# ETH-PHY.net
KiCad netlist of a schematic drawn in Altium Designer
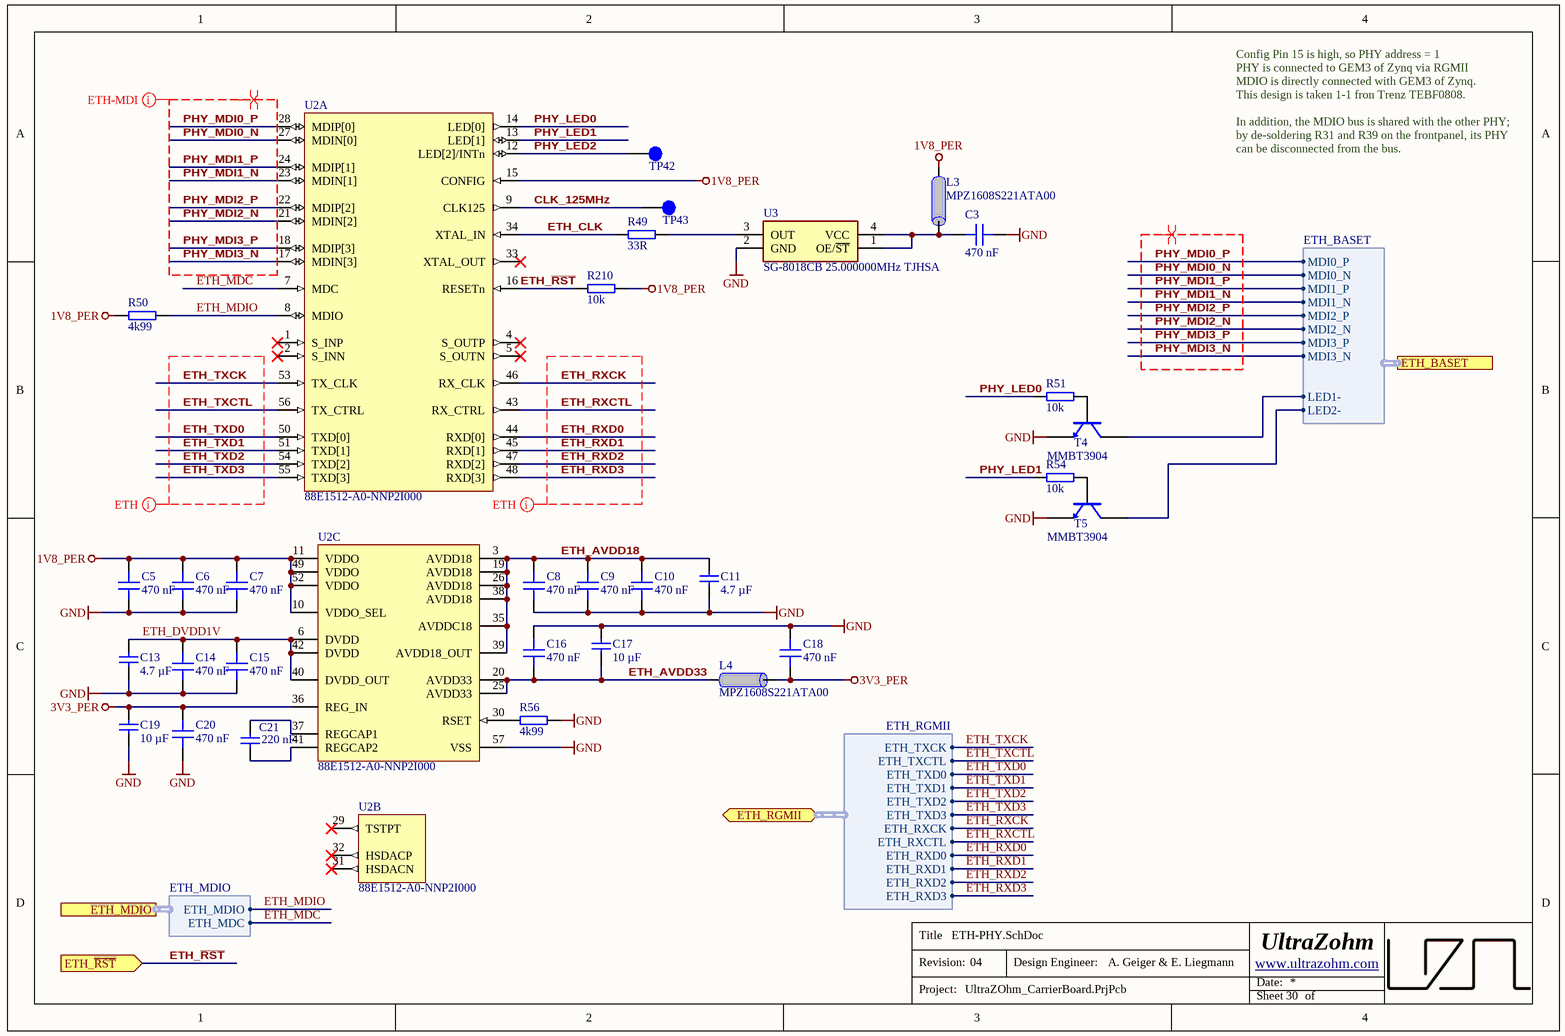
[diagram p0: ETH-PHY.SchDoc]

(export (version "E")
  (design (tool "Eeschema 10.0.6"))
  (components
    (comp (ref "C3")
      (value "470 nF")
      (footprint "C_0603_TE")
      (description "Capacitor 0603, 50 VDC, 470 nF, X5R")
      (fields
        (field (name "MANUFACTURER PART NUMBER") "CL10A474KB8NNNC")
        (field (name "MANUFACTURER") "Samsung Electro-Mechanics")
        (field (name "CREATED FROM") "AGeiger")
      )
      (libsource (lib "user") (part "Capacitor"))
    )
    (comp (ref "C5")
      (value "470 nF")
      (footprint "C_0603_TE")
      (description "Capacitor 0603, 50 VDC, 470 nF, X5R")
      (fields
        (field (name "MANUFACTURER PART NUMBER") "CL10A474KB8NNNC")
        (field (name "MANUFACTURER") "Samsung Electro-Mechanics")
        (field (name "CREATED FROM") "AGeiger")
      )
      (libsource (lib "user") (part "Capacitor"))
    )
    (comp (ref "C6")
      (value "470 nF")
      (footprint "C_0603_TE")
      (description "Capacitor 0603, 50 VDC, 470 nF, X5R")
      (fields
        (field (name "MANUFACTURER PART NUMBER") "CL10A474KB8NNNC")
        (field (name "MANUFACTURER") "Samsung Electro-Mechanics")
        (field (name "CREATED FROM") "AGeiger")
      )
      (libsource (lib "user") (part "Capacitor"))
    )
    (comp (ref "C7")
      (value "470 nF")
      (footprint "C_0603_TE")
      (description "Capacitor 0603, 50 VDC, 470 nF, X5R")
      (fields
        (field (name "MANUFACTURER PART NUMBER") "CL10A474KB8NNNC")
        (field (name "MANUFACTURER") "Samsung Electro-Mechanics")
        (field (name "CREATED FROM") "AGeiger")
      )
      (libsource (lib "user") (part "Capacitor"))
    )
    (comp (ref "C8")
      (value "470 nF")
      (footprint "C_0603_TE")
      (description "Capacitor 0603, 50 VDC, 470 nF, X5R")
      (fields
        (field (name "MANUFACTURER PART NUMBER") "CL10A474KB8NNNC")
        (field (name "MANUFACTURER") "Samsung Electro-Mechanics")
        (field (name "CREATED FROM") "AGeiger")
      )
      (libsource (lib "user") (part "Capacitor"))
    )
    (comp (ref "C9")
      (value "470 nF")
      (footprint "C_0603_TE")
      (description "Capacitor 0603, 50 VDC, 470 nF, X5R")
      (fields
        (field (name "MANUFACTURER PART NUMBER") "CL10A474KB8NNNC")
        (field (name "MANUFACTURER") "Samsung Electro-Mechanics")
        (field (name "CREATED FROM") "AGeiger")
      )
      (libsource (lib "user") (part "Capacitor"))
    )
    (comp (ref "C10")
      (value "470 nF")
      (footprint "C_0603_TE")
      (description "Capacitor 0603, 50 VDC, 470 nF, X5R")
      (fields
        (field (name "MANUFACTURER PART NUMBER") "CL10A474KB8NNNC")
        (field (name "MANUFACTURER") "Samsung Electro-Mechanics")
        (field (name "CREATED FROM") "AGeiger")
      )
      (libsource (lib "user") (part "Capacitor"))
    )
    (comp (ref "C11")
      (value "4.7 µF")
      (footprint "C_0603_TE")
      (description "Generic capacitor")
      (fields
        (field (name "TOLERANCE") "10 %")
        (field (name "MANUFACTURER PART NUMBER") "UZgen_C_0603_4.7uF_16V_X5R")
        (field (name "CREATED FROM") "MGeier")
      )
      (libsource (lib "user") (part "CAP-NP"))
    )
    (comp (ref "C13")
      (value "4.7 µF")
      (footprint "C_0603_TE")
      (description "Generic capacitor")
      (fields
        (field (name "TOLERANCE") "10 %")
        (field (name "MANUFACTURER PART NUMBER") "UZgen_C_0603_4.7uF_16V_X5R")
        (field (name "CREATED FROM") "MGeier")
      )
      (libsource (lib "user") (part "CAP-NP"))
    )
    (comp (ref "C14")
      (value "470 nF")
      (footprint "C_0603_TE")
      (description "Capacitor 0603, 50 VDC, 470 nF, X5R")
      (fields
        (field (name "MANUFACTURER PART NUMBER") "CL10A474KB8NNNC")
        (field (name "MANUFACTURER") "Samsung Electro-Mechanics")
        (field (name "CREATED FROM") "AGeiger")
      )
      (libsource (lib "user") (part "Capacitor"))
    )
    (comp (ref "C15")
      (value "470 nF")
      (footprint "C_0603_TE")
      (description "Capacitor 0603, 50 VDC, 470 nF, X5R")
      (fields
        (field (name "MANUFACTURER PART NUMBER") "CL10A474KB8NNNC")
        (field (name "MANUFACTURER") "Samsung Electro-Mechanics")
        (field (name "CREATED FROM") "AGeiger")
      )
      (libsource (lib "user") (part "Capacitor"))
    )
    (comp (ref "C16")
      (value "470 nF")
      (footprint "C_0603_TE")
      (description "Capacitor 0603, 50 VDC, 470 nF, X5R")
      (fields
        (field (name "MANUFACTURER PART NUMBER") "CL10A474KB8NNNC")
        (field (name "MANUFACTURER") "Samsung Electro-Mechanics")
        (field (name "CREATED FROM") "AGeiger")
      )
      (libsource (lib "user") (part "Capacitor"))
    )
    (comp (ref "C17")
      (value "10 µF")
      (footprint "C_0603_TE")
      (description "Generic capacitor")
      (fields
        (field (name "MANUFACTURER PART NUMBER") "UZgen_C_0603_10uF_6.3V_X7R")
        (field (name "MANUFACTURER") "UZgen")
        (field (name "CREATED FROM") "UZgenTool")
      )
      (libsource (lib "user") (part "CAP-NP"))
    )
    (comp (ref "C18")
      (value "470 nF")
      (footprint "C_0603_TE")
      (description "Capacitor 0603, 50 VDC, 470 nF, X5R")
      (fields
        (field (name "MANUFACTURER PART NUMBER") "CL10A474KB8NNNC")
        (field (name "MANUFACTURER") "Samsung Electro-Mechanics")
        (field (name "CREATED FROM") "AGeiger")
      )
      (libsource (lib "user") (part "Capacitor"))
    )
    (comp (ref "C19")
      (value "10 µF")
      (footprint "C_0603_TE")
      (description "Generic capacitor")
      (fields
        (field (name "MANUFACTURER PART NUMBER") "UZgen_C_0603_10uF_6.3V_X7R")
        (field (name "MANUFACTURER") "UZgen")
        (field (name "CREATED FROM") "UZgenTool")
      )
      (libsource (lib "user") (part "CAP-NP"))
    )
    (comp (ref "C20")
      (value "470 nF")
      (footprint "C_0603_TE")
      (description "Capacitor 0603, 50 VDC, 470 nF, X5R")
      (fields
        (field (name "MANUFACTURER PART NUMBER") "CL10A474KB8NNNC")
        (field (name "MANUFACTURER") "Samsung Electro-Mechanics")
        (field (name "CREATED FROM") "AGeiger")
      )
      (libsource (lib "user") (part "Capacitor"))
    )
    (comp (ref "C21")
      (value "220 nF")
      (footprint "C_0603_TE")
      (description "Generic capacitor")
      (fields
        (field (name "TOLERANCE") "10 %")
        (field (name "VOLTAGE") "50V")
        (field (name "CREATED FROM") "UZgenTool")
      )
      (libsource (lib "user") (part "CAP-NP"))
    )
    (comp (ref "L3")
      (value "MPZ1608S221ATA00")
      (footprint "RES 0603_1608")
      (description "Ferritperle, 0603, 220 ohm, 2.2 A, Baureihe MPZ, 0.05 ohm, ± 25%")
      (fields
        (field (name "MANUFACTURER") "TDK")
        (field (name "LCSC PART NUMBER") "C76815")
        (field (name "CREATED FROM") "MGremer")
      )
      (libsource (lib "") (part "Ferrite_Bead_1"))
    )
    (comp (ref "L4")
      (value "MPZ1608S221ATA00")
      (footprint "RES 0603_1608")
      (description "Ferritperle, 0603, 220 ohm, 2.2 A, Baureihe MPZ, 0.05 ohm, ± 25%")
      (fields
        (field (name "MANUFACTURER") "TDK")
        (field (name "LCSC PART NUMBER") "C76815")
        (field (name "CREATED FROM") "MGremer")
      )
      (libsource (lib "user") (part "Ferrite_Bead"))
    )
    (comp (ref "R49")
      (value "33R")
      (footprint "R_0603_TE")
      (description "Generic resistor")
      (fields
        (field (name "TOLERANCE") "1 %")
        (field (name "MANUFACTURER PART NUMBER") "UZgen_R_0603_33R")
        (field (name "CREATED FROM") "UZgenTool")
      )
      (libsource (lib "user") (part "RES"))
    )
    (comp (ref "R50")
      (value "4k99")
      (footprint "RES 0603_1608")
      (fields
        (field (name "TOLERANCE") "1%")
        (field (name "MANUFACTURER PART NUMBER") "0603WAF4991T5E")
        (field (name "MANUFACTURER") "UNI-ROYAL(Uniroyal Elec)")
        (field (name "CREATED FROM") "NDiringer")
      )
      (libsource (lib "user") (part "Resistor"))
    )
    (comp (ref "R51")
      (value "10k")
      (footprint "R_0603_TE")
      (description "Generic resistor")
      (fields
        (field (name "TOLERANCE") "1 %")
        (field (name "MANUFACTURER PART NUMBER") "UZgen_R_0603_10k")
        (field (name "CREATED FROM") "AGeiger")
      )
      (libsource (lib "user") (part "RES"))
    )
    (comp (ref "R54")
      (value "10k")
      (footprint "R_0603_TE")
      (description "Generic resistor")
      (fields
        (field (name "TOLERANCE") "1 %")
        (field (name "MANUFACTURER PART NUMBER") "UZgen_R_0603_10k")
        (field (name "CREATED FROM") "AGeiger")
      )
      (libsource (lib "user") (part "RES"))
    )
    (comp (ref "R56")
      (value "4k99")
      (footprint "RES 0603_1608")
      (fields
        (field (name "TOLERANCE") "1%")
        (field (name "MANUFACTURER PART NUMBER") "0603WAF4991T5E")
        (field (name "MANUFACTURER") "UNI-ROYAL(Uniroyal Elec)")
        (field (name "CREATED FROM") "NDiringer")
      )
      (libsource (lib "user") (part "Resistor"))
    )
    (comp (ref "R210")
      (value "10k")
      (footprint "R_0603_TE")
      (description "Generic resistor")
      (fields
        (field (name "TOLERANCE") "1 %")
        (field (name "MANUFACTURER PART NUMBER") "UZgen_R_0603_10k")
        (field (name "CREATED FROM") "AGeiger")
      )
      (libsource (lib "user") (part "RES"))
    )
    (comp (ref "T4")
      (value "MMBT3904")
      (footprint "SOT95P280X145-3N")
      (fields
        (field (name "MANUFACTURER") "Jiangsu Changjing Electronics Technology Co., Ltd.")
        (field (name "LCSC PART NUMBER") "C20526")
        (field (name "CREATED FROM") "NDiringer")
      )
      (libsource (lib "user") (part "NPN-SOT23"))
    )
    (comp (ref "T5")
      (value "MMBT3904")
      (footprint "SOT95P280X145-3N")
      (fields
        (field (name "MANUFACTURER") "Jiangsu Changjing Electronics Technology Co., Ltd.")
        (field (name "LCSC PART NUMBER") "C20526")
        (field (name "CREATED FROM") "NDiringer")
      )
      (libsource (lib "user") (part "NPN-SOT23"))
    )
    (comp (ref "TP42")
      (value "Testpoint 1mm")
      (footprint "TP_1mm")
      (fields
        (field (name "MANUFACTURER PART NUMBER") "NULL")
        (field (name "CREATED") "2018_06_25_AGeiger")
        (field (name "CREATED FROM") "AGeiger")
      )
      (libsource (lib "user") (part "TP_1mm"))
    )
    (comp (ref "TP43")
      (value "Testpoint 1mm")
      (footprint "TP_1mm")
      (fields
        (field (name "MANUFACTURER PART NUMBER") "NULL")
        (field (name "CREATED") "2018_06_25_AGeiger")
        (field (name "CREATED FROM") "AGeiger")
      )
      (libsource (lib "user") (part "TP_1mm"))
    )
    (comp (ref "U2")
      (value "88E1512-A0-NNP2I000")
      (footprint "QFN50P800X800X100-57N")
      (description "Ethernet ICs Single-Port EEE GE PHY w/SGMII in 56-pin QFN")
      (fields
        (field (name "MANUFACTURER") "Marvell")
        (field (name "LCSC PART NUMBER") "C713256")
        (field (name "CREATED FROM") "MGremer")
      )
      (libsource (lib "user") (part "88E1512"))
    )
    (comp (ref "U3")
      (value "SG-8018CB 25.000000MHz TJHSA")
      (footprint "SMD5032-4P")
      (description "±50ppm 1.8V~3.3V 25MHz SMD5032-4P Programmable Oscillators ROHS")
      (fields
        (field (name "MANUFACTURER") "Seiko Epson")
        (field (name "LCSC PART NUMBER") "C390471")
        (field (name "CREATED FROM") "FRosner")
      )
      (libsource (lib "user") (part "SG-8018CB"))
    )
  )
  (nets
    (net (code "3") (name "/CLK_125MHz") (class "Default")
      (node (ref "TP43") (pin "1") (pintype "passive"))
      (node (ref "U2") (pin "9") (pinfunction "CLK125_9") (pintype "output"))
    )
    (net (code "4") (name "/ETH_AVDD18") (class "Default")
      (node (ref "C10") (pin "1") (pinfunction "1_1") (pintype "passive"))
      (node (ref "C11") (pin "1") (pinfunction "1_1") (pintype "passive"))
      (node (ref "C8") (pin "1") (pinfunction "1_1") (pintype "passive"))
      (node (ref "C9") (pin "1") (pinfunction "1_1") (pintype "passive"))
      (node (ref "U2") (pin "19") (pinfunction "AVDD18_19") (pintype "power_in"))
      (node (ref "U2") (pin "26") (pinfunction "AVDD18_26") (pintype "power_in"))
      (node (ref "U2") (pin "3") (pinfunction "AVDD18_3") (pintype "power_in"))
      (node (ref "U2") (pin "35") (pinfunction "AVDDC18_35") (pintype "power_in"))
      (node (ref "U2") (pin "38") (pinfunction "AVDD18_38") (pintype "power_in"))
      (node (ref "U2") (pin "39") (pinfunction "AVDD18_OUT_39") (pintype "power_in"))
    )
    (net (code "5") (name "/ETH_AVDD33") (class "Default")
      (node (ref "C16") (pin "2") (pinfunction "2_2") (pintype "passive"))
      (node (ref "C17") (pin "2") (pinfunction "2_2") (pintype "passive"))
      (node (ref "L4") (pin "1") (pinfunction "1_1") (pintype "passive"))
      (node (ref "U2") (pin "20") (pinfunction "AVDD33_20") (pintype "power_in"))
      (node (ref "U2") (pin "25") (pinfunction "AVDD33_25") (pintype "power_in"))
    )
    (net (code "6") (name "/ETH_CLK") (class "Default")
      (node (ref "R49") (pin "1") (pinfunction "1_1") (pintype "passive"))
      (node (ref "U2") (pin "34") (pinfunction "XTAL_IN_34") (pintype "input"))
    )
    (net (code "7") (name "/ETH_DVDD1V") (class "Default")
      (node (ref "C13") (pin "1") (pinfunction "1_1") (pintype "passive"))
      (node (ref "C14") (pin "1") (pinfunction "1_1") (pintype "passive"))
      (node (ref "C15") (pin "1") (pinfunction "1_1") (pintype "passive"))
      (node (ref "U2") (pin "40") (pinfunction "DVDD_OUT_40") (pintype "power_in"))
      (node (ref "U2") (pin "42") (pinfunction "DVDD_42") (pintype "power_in"))
      (node (ref "U2") (pin "6") (pinfunction "DVDD_6") (pintype "power_in"))
    )
    (net (code "8") (name "/ETH_MDC") (class "Default")
      (node (ref "U2") (pin "7") (pinfunction "MDC_7") (pintype "input"))
    )
    (net (code "9") (name "/ETH_MDIO") (class "Default")
      (node (ref "R50") (pin "2") (pinfunction "2_2") (pintype "passive"))
      (node (ref "U2") (pin "8") (pinfunction "MDIO_8") (pintype "bidirectional"))
    )
    (net (code "10") (name "/ETH_RXCK") (class "Default")
      (node (ref "U2") (pin "46") (pinfunction "RX_CLK_46") (pintype "output"))
    )
    (net (code "11") (name "/ETH_RXCTL") (class "Default")
      (node (ref "U2") (pin "43") (pinfunction "RX_CTRL_43") (pintype "output"))
    )
    (net (code "12") (name "/ETH_RXD0") (class "Default")
      (node (ref "U2") (pin "44") (pinfunction "RXD[0]_44") (pintype "output"))
    )
    (net (code "13") (name "/ETH_RXD1") (class "Default")
      (node (ref "U2") (pin "45") (pinfunction "RXD[1]_45") (pintype "output"))
    )
    (net (code "14") (name "/ETH_RXD2") (class "Default")
      (node (ref "U2") (pin "47") (pinfunction "RXD[2]_47") (pintype "output"))
    )
    (net (code "15") (name "/ETH_RXD3") (class "Default")
      (node (ref "U2") (pin "48") (pinfunction "RXD[3]_48") (pintype "output"))
    )
    (net (code "16") (name "/ETH_TXCK") (class "Default")
      (node (ref "U2") (pin "53") (pinfunction "TX_CLK_53") (pintype "input"))
    )
    (net (code "17") (name "/ETH_TXCTL") (class "Default")
      (node (ref "U2") (pin "56") (pinfunction "TX_CTRL_56") (pintype "input"))
    )
    (net (code "18") (name "/ETH_TXD0") (class "Default")
      (node (ref "U2") (pin "50") (pinfunction "TXD[0]_50") (pintype "input"))
    )
    (net (code "19") (name "/ETH_TXD1") (class "Default")
      (node (ref "U2") (pin "51") (pinfunction "TXD[1]_51") (pintype "input"))
    )
    (net (code "20") (name "/ETH_TXD2") (class "Default")
      (node (ref "U2") (pin "54") (pinfunction "TXD[2]_54") (pintype "input"))
    )
    (net (code "21") (name "/ETH_TXD3") (class "Default")
      (node (ref "U2") (pin "55") (pinfunction "TXD[3]_55") (pintype "input"))
    )
    (net (code "22") (name "/ETH_~{RST}") (class "Default")
      (node (ref "R210") (pin "1") (pinfunction "1_1") (pintype "passive"))
      (node (ref "U2") (pin "16") (pinfunction "RESETn_16") (pintype "input"))
    )
    (net (code "23") (name "/LED1-") (class "Default")
      (node (ref "T4") (pin "3") (pinfunction "COLLECTOR_3") (pintype "passive"))
    )
    (net (code "24") (name "/LED2-") (class "Default")
      (node (ref "T5") (pin "3") (pinfunction "COLLECTOR_3") (pintype "passive"))
    )
    (net (code "25") (name "/PHY_LED0") (class "Default")
      (node (ref "R51") (pin "1") (pinfunction "1_1") (pintype "passive"))
      (node (ref "U2") (pin "14") (pinfunction "LED[0]_14") (pintype "output"))
    )
    (net (code "26") (name "/PHY_LED1") (class "Default")
      (node (ref "R54") (pin "1") (pinfunction "1_1") (pintype "passive"))
      (node (ref "U2") (pin "13") (pinfunction "LED[1]_13") (pintype "bidirectional"))
    )
    (net (code "27") (name "/PHY_LED2") (class "Default")
      (node (ref "TP42") (pin "1") (pintype "passive"))
      (node (ref "U2") (pin "12") (pinfunction "LED[2]/INTn_12") (pintype "bidirectional"))
    )
    (net (code "28") (name "/PHY_MDI0_N") (class "Default")
      (node (ref "U2") (pin "27") (pinfunction "MDIN[0]_27") (pintype "bidirectional"))
    )
    (net (code "29") (name "/PHY_MDI0_P") (class "Default")
      (node (ref "U2") (pin "28") (pinfunction "MDIP[0]_28") (pintype "bidirectional"))
    )
    (net (code "30") (name "/PHY_MDI1_N") (class "Default")
      (node (ref "U2") (pin "23") (pinfunction "MDIN[1]_23") (pintype "bidirectional"))
    )
    (net (code "31") (name "/PHY_MDI1_P") (class "Default")
      (node (ref "U2") (pin "24") (pinfunction "MDIP[1]_24") (pintype "bidirectional"))
    )
    (net (code "32") (name "/PHY_MDI2_N") (class "Default")
      (node (ref "U2") (pin "21") (pinfunction "MDIN[2]_21") (pintype "bidirectional"))
    )
    (net (code "33") (name "/PHY_MDI2_P") (class "Default")
      (node (ref "U2") (pin "22") (pinfunction "MDIP[2]_22") (pintype "bidirectional"))
    )
    (net (code "34") (name "/PHY_MDI3_N") (class "Default")
      (node (ref "U2") (pin "17") (pinfunction "MDIN[3]_17") (pintype "bidirectional"))
    )
    (net (code "35") (name "/PHY_MDI3_P") (class "Default")
      (node (ref "U2") (pin "18") (pinfunction "MDIP[3]_18") (pintype "bidirectional"))
    )
    (net (code "39") (name "1V8_PER") (class "Default")
      (node (ref "C5") (pin "1") (pinfunction "1_1") (pintype "passive"))
      (node (ref "C6") (pin "1") (pinfunction "1_1") (pintype "passive"))
      (node (ref "C7") (pin "1") (pinfunction "1_1") (pintype "passive"))
      (node (ref "L3") (pin "1") (pinfunction "1_1") (pintype "passive"))
      (node (ref "R210") (pin "2") (pinfunction "2_2") (pintype "passive"))
      (node (ref "R50") (pin "1") (pinfunction "1_1") (pintype "passive"))
      (node (ref "U2") (pin "10") (pinfunction "VDDO_SEL_10") (pintype "power_in"))
      (node (ref "U2") (pin "11") (pinfunction "VDDO_11") (pintype "power_in"))
      (node (ref "U2") (pin "15") (pinfunction "CONFIG_15") (pintype "input"))
      (node (ref "U2") (pin "49") (pinfunction "VDDO_49") (pintype "power_in"))
      (node (ref "U2") (pin "52") (pinfunction "VDDO_52") (pintype "power_in"))
    )
    (net (code "40") (name "3V3_PER") (class "Default")
      (node (ref "C18") (pin "2") (pinfunction "2_2") (pintype "passive"))
      (node (ref "C19") (pin "1") (pinfunction "1_1") (pintype "passive"))
      (node (ref "C20") (pin "1") (pinfunction "1_1") (pintype "passive"))
      (node (ref "L4") (pin "2") (pinfunction "2_2") (pintype "passive"))
      (node (ref "U2") (pin "36") (pinfunction "REG_IN_36") (pintype "power_in"))
    )
    (net (code "41") (name "GND") (class "Default")
      (node (ref "C10") (pin "2") (pinfunction "2_2") (pintype "passive"))
      (node (ref "C11") (pin "2") (pinfunction "2_2") (pintype "passive"))
      (node (ref "C13") (pin "2") (pinfunction "2_2") (pintype "passive"))
      (node (ref "C14") (pin "2") (pinfunction "2_2") (pintype "passive"))
      (node (ref "C15") (pin "2") (pinfunction "2_2") (pintype "passive"))
      (node (ref "C16") (pin "1") (pinfunction "1_1") (pintype "passive"))
      (node (ref "C17") (pin "1") (pinfunction "1_1") (pintype "passive"))
      (node (ref "C18") (pin "1") (pinfunction "1_1") (pintype "passive"))
      (node (ref "C19") (pin "2") (pinfunction "2_2") (pintype "passive"))
      (node (ref "C20") (pin "2") (pinfunction "2_2") (pintype "passive"))
      (node (ref "C3") (pin "1") (pinfunction "1_1") (pintype "passive"))
      (node (ref "C5") (pin "2") (pinfunction "2_2") (pintype "passive"))
      (node (ref "C6") (pin "2") (pinfunction "2_2") (pintype "passive"))
      (node (ref "C7") (pin "2") (pinfunction "2_2") (pintype "passive"))
      (node (ref "C8") (pin "2") (pinfunction "2_2") (pintype "passive"))
      (node (ref "C9") (pin "2") (pinfunction "2_2") (pintype "passive"))
      (node (ref "R56") (pin "2") (pinfunction "2_2") (pintype "passive"))
      (node (ref "T4") (pin "2") (pinfunction "EMITTER_2") (pintype "passive"))
      (node (ref "T5") (pin "2") (pinfunction "EMITTER_2") (pintype "passive"))
      (node (ref "U2") (pin "57") (pinfunction "VSS_57") (pintype "power_in"))
      (node (ref "U3") (pin "2") (pinfunction "GND_2") (pintype "passive"))
    )
    (net (code "42") (name "Net-(T4-BASIS)") (class "Default")
      (node (ref "R51") (pin "2") (pinfunction "2_2") (pintype "passive"))
      (node (ref "T4") (pin "1") (pinfunction "BASIS_1") (pintype "passive"))
    )
    (net (code "43") (name "Net-(T5-BASIS)") (class "Default")
      (node (ref "R54") (pin "2") (pinfunction "2_2") (pintype "passive"))
      (node (ref "T5") (pin "1") (pinfunction "BASIS_1") (pintype "passive"))
    )
    (net (code "44") (name "Net-(U2C-REGCAP1)") (class "Default")
      (node (ref "C21") (pin "1") (pinfunction "1_1") (pintype "passive"))
      (node (ref "U2") (pin "37") (pinfunction "REGCAP1_37") (pintype "passive"))
    )
    (net (code "45") (name "Net-(U2C-REGCAP2)") (class "Default")
      (node (ref "C21") (pin "2") (pinfunction "2_2") (pintype "passive"))
      (node (ref "U2") (pin "41") (pinfunction "REGCAP2_41") (pintype "passive"))
    )
    (net (code "46") (name "Net-(U2C-RSET)") (class "Default")
      (node (ref "R56") (pin "1") (pinfunction "1_1") (pintype "passive"))
      (node (ref "U2") (pin "30") (pinfunction "RSET_30") (pintype "input"))
    )
    (net (code "47") (name "Net-(U3-OE{slash}~{ST})") (class "Default")
      (node (ref "C3") (pin "2") (pinfunction "2_2") (pintype "passive"))
      (node (ref "L3") (pin "2") (pinfunction "2_2") (pintype "passive"))
      (node (ref "U3") (pin "1") (pinfunction "OE/~{ST}_1") (pintype "passive"))
      (node (ref "U3") (pin "4") (pinfunction "VCC_4") (pintype "passive"))
    )
    (net (code "48") (name "Net-(U3-OUT)") (class "Default")
      (node (ref "R49") (pin "2") (pinfunction "2_2") (pintype "passive"))
      (node (ref "U3") (pin "3") (pinfunction "OUT_3") (pintype "passive"))
    )
    (net (code "49") (name "unconnected-(U2A-S_INN-Pad2)") (class "Default")
      (node (ref "U2") (pin "2") (pinfunction "S_INN_2") (pintype "input+no_connect"))
    )
    (net (code "50") (name "unconnected-(U2A-S_INP-Pad1)") (class "Default")
      (node (ref "U2") (pin "1") (pinfunction "S_INP_1") (pintype "input+no_connect"))
    )
    (net (code "51") (name "unconnected-(U2A-S_OUTN-Pad5)") (class "Default")
      (node (ref "U2") (pin "5") (pinfunction "S_OUTN_5") (pintype "output+no_connect"))
    )
    (net (code "52") (name "unconnected-(U2A-S_OUTP-Pad4)") (class "Default")
      (node (ref "U2") (pin "4") (pinfunction "S_OUTP_4") (pintype "output+no_connect"))
    )
    (net (code "53") (name "unconnected-(U2A-XTAL_OUT-Pad33)") (class "Default")
      (node (ref "U2") (pin "33") (pinfunction "XTAL_OUT_33") (pintype "output+no_connect"))
    )
    (net (code "54") (name "unconnected-(U2B-HSDACN-Pad31)") (class "Default")
      (node (ref "U2") (pin "31") (pinfunction "HSDACN_31") (pintype "output+no_connect"))
    )
    (net (code "55") (name "unconnected-(U2B-HSDACP-Pad32)") (class "Default")
      (node (ref "U2") (pin "32") (pinfunction "HSDACP_32") (pintype "output+no_connect"))
    )
    (net (code "56") (name "unconnected-(U2B-TSTPT-Pad29)") (class "Default")
      (node (ref "U2") (pin "29") (pinfunction "TSTPT_29") (pintype "output+no_connect"))
    )
  )
)
